# LIC_rack_TS-01.net
KiCad netlist of a schematic drawn in EAGLE
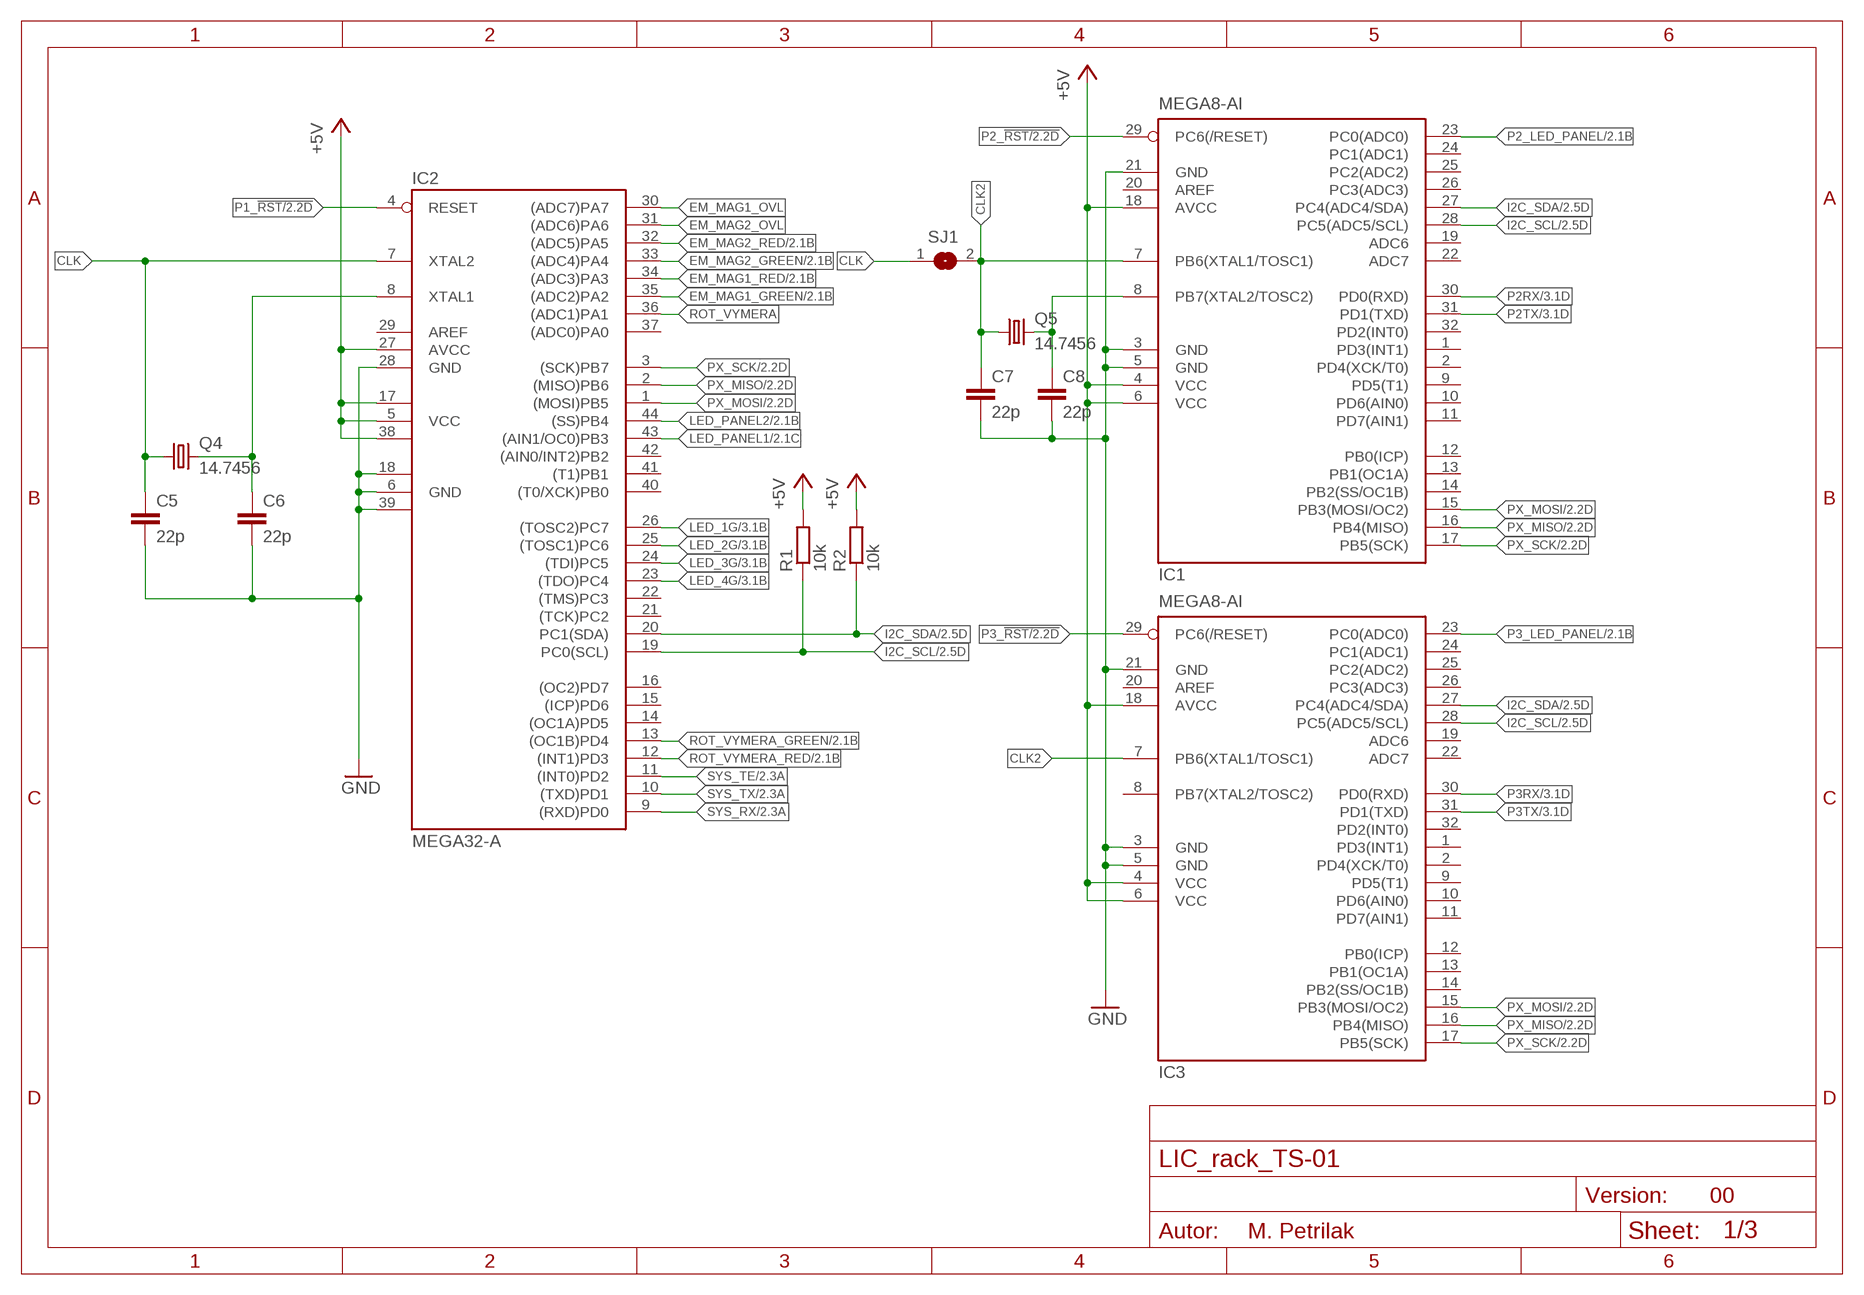
[diagram p0: schematic, sheet 1]
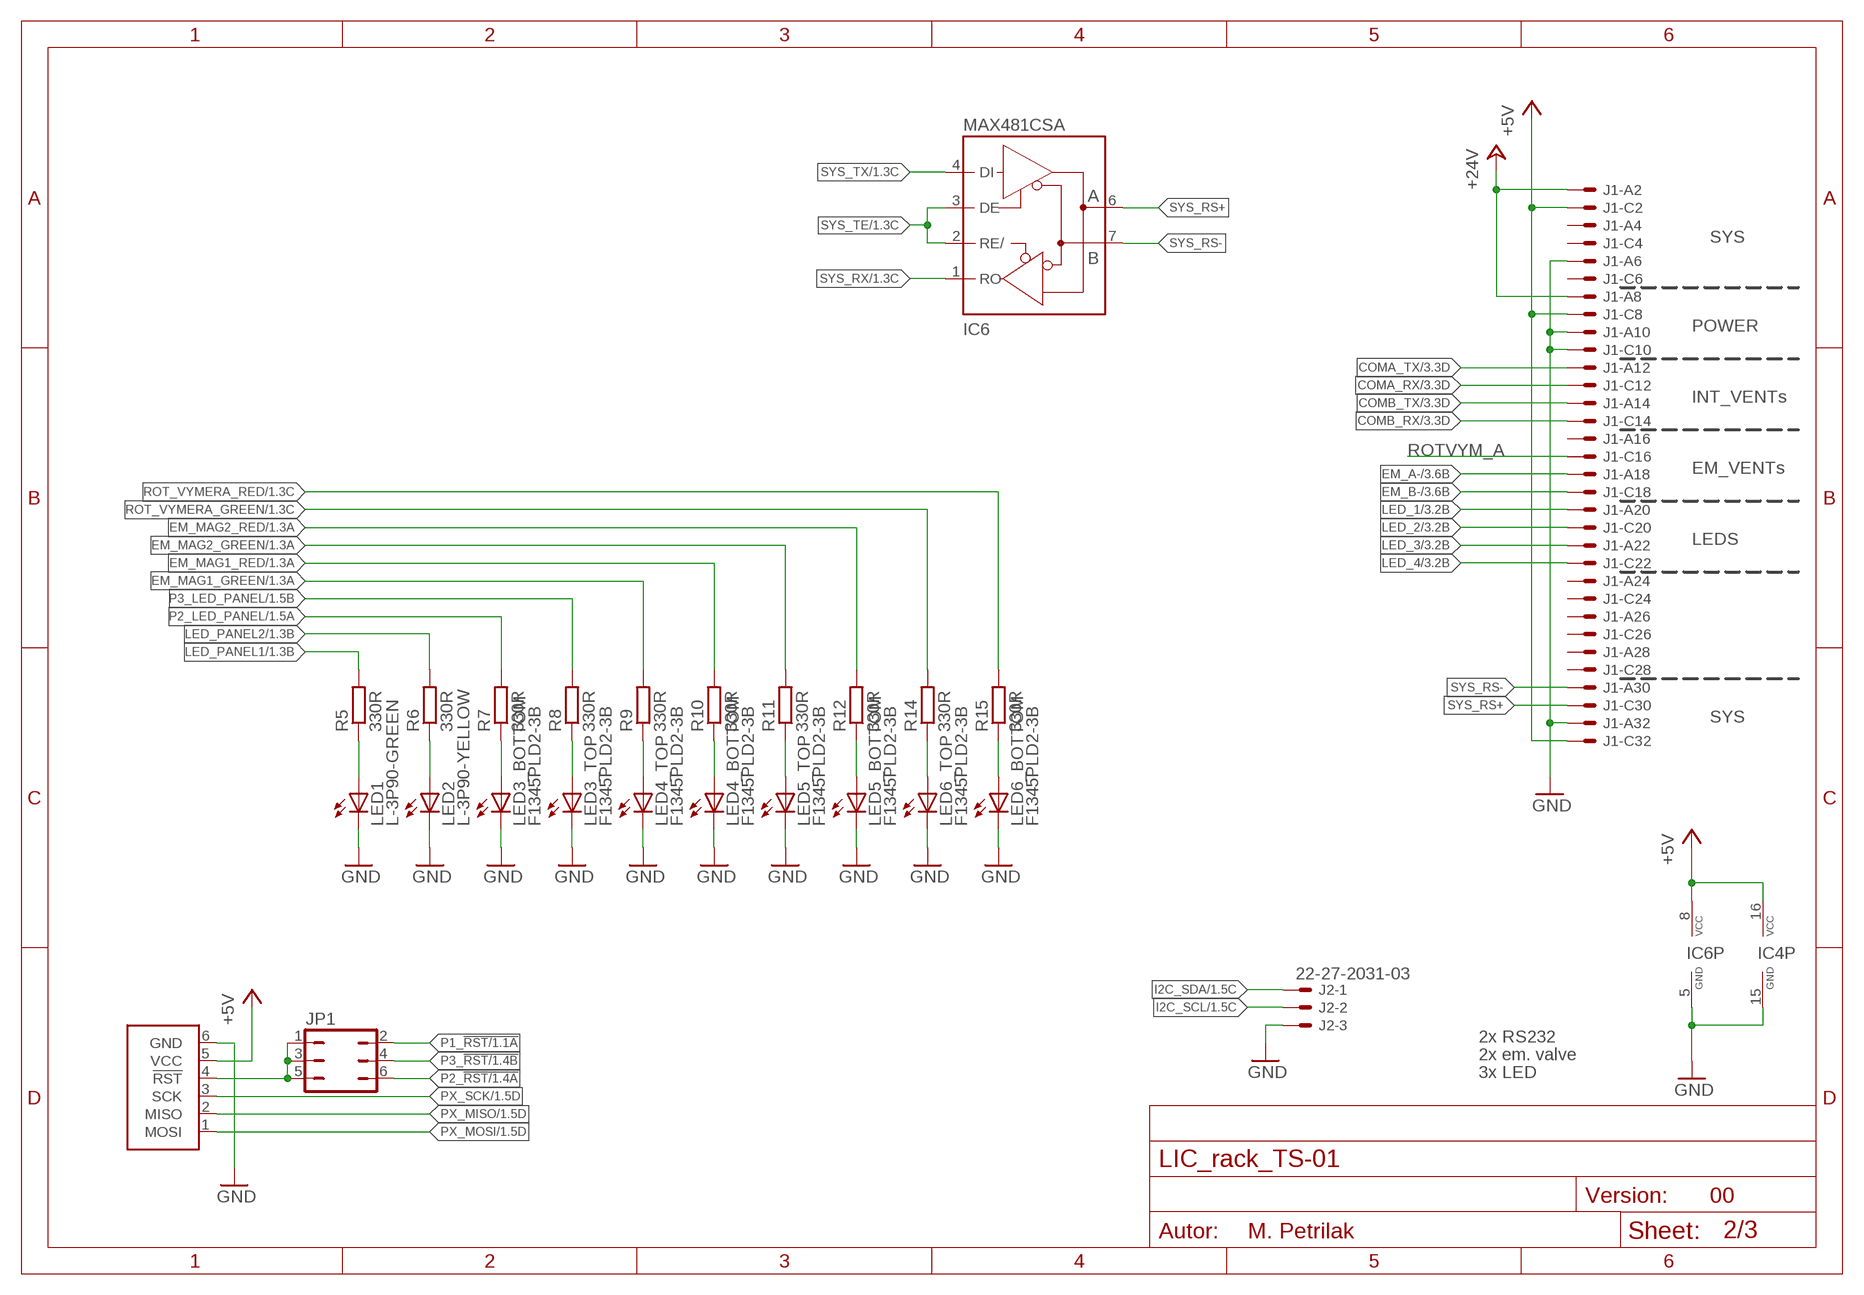
[diagram p1: schematic, sheet 2]
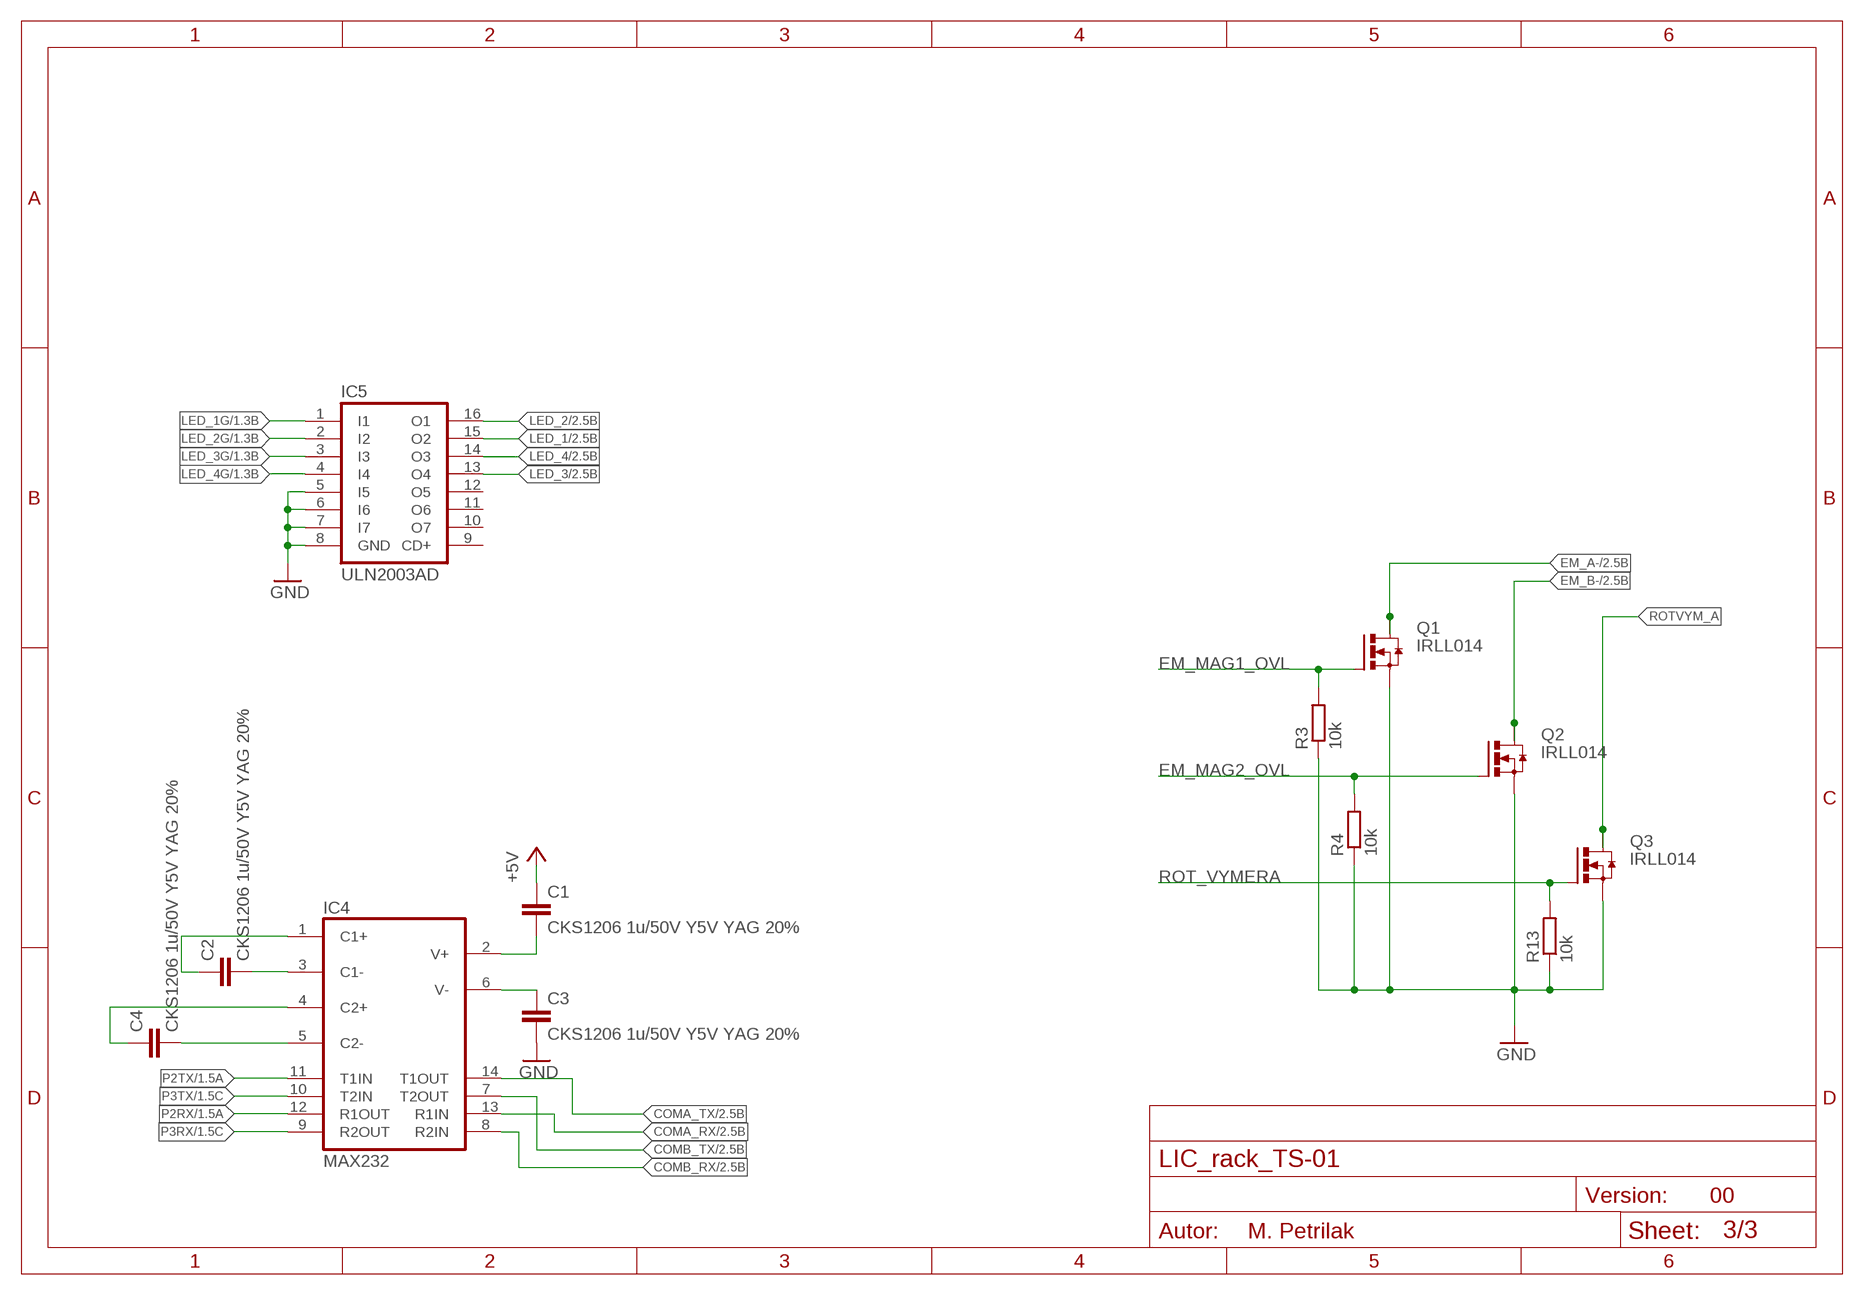
[diagram p2: schematic, sheet 3]

(export (version "E")
  (design (tool "Eeschema 10.0.6"))
  (components
    (comp (ref "C1")
      (value "CKS1206 1u/50V Y5V YAG 20%")
      (footprint "eagle-import:C1206")
      (libsource (lib "eagle-import") (part "C-EUC1206"))
    )
    (comp (ref "C2")
      (value "CKS1206 1u/50V Y5V YAG 20%")
      (footprint "eagle-import:C1206")
      (libsource (lib "eagle-import") (part "C-EUC1206"))
    )
    (comp (ref "C3")
      (value "CKS1206 1u/50V Y5V YAG 20%")
      (footprint "eagle-import:C1206")
      (libsource (lib "eagle-import") (part "C-EUC1206"))
    )
    (comp (ref "C4")
      (value "CKS1206 1u/50V Y5V YAG 20%")
      (footprint "eagle-import:C1206")
      (libsource (lib "eagle-import") (part "C-EUC1206"))
    )
    (comp (ref "IC4")
      (value "MAX232")
      (footprint "eagle-import:DIL16")
      (libsource (lib "eagle-import") (part "MAX232"))
    )
    (comp (ref "IC5")
      (value "ULN2003AD")
      (footprint "eagle-import:SO16")
      (libsource (lib "eagle-import") (part "ULN2003AD"))
    )
    (comp (ref "Q1")
      (value "IRLL014")
      (footprint "eagle-import:SOT223")
      (libsource (lib "eagle-import") (part "IRLL014"))
    )
    (comp (ref "Q2")
      (value "IRLL014")
      (footprint "eagle-import:SOT223")
      (libsource (lib "eagle-import") (part "IRLL014"))
    )
    (comp (ref "Q3")
      (value "IRLL014")
      (footprint "eagle-import:SOT223")
      (libsource (lib "eagle-import") (part "IRLL014"))
    )
    (comp (ref "R3")
      (value "10k")
      (footprint "eagle-import:R1206")
      (libsource (lib "eagle-import") (part "R-EU_R1206"))
    )
    (comp (ref "R4")
      (value "10k")
      (footprint "eagle-import:R1206")
      (libsource (lib "eagle-import") (part "R-EU_R1206"))
    )
    (comp (ref "R13")
      (value "10k")
      (footprint "eagle-import:R1206")
      (libsource (lib "eagle-import") (part "R-EU_R1206"))
    )
    (comp (ref "C5")
      (value "22p")
      (footprint "eagle-import:C0805")
      (libsource (lib "eagle-import") (part "C-EUC0805"))
    )
    (comp (ref "C6")
      (value "22p")
      (footprint "eagle-import:C0805")
      (libsource (lib "eagle-import") (part "C-EUC0805"))
    )
    (comp (ref "C7")
      (value "22p")
      (footprint "eagle-import:C0805")
      (libsource (lib "eagle-import") (part "C-EUC0805"))
    )
    (comp (ref "C8")
      (value "22p")
      (footprint "eagle-import:C0805")
      (libsource (lib "eagle-import") (part "C-EUC0805"))
    )
    (comp (ref "IC1")
      (value "MEGA8-AI")
      (footprint "eagle-import:TQFP32-08")
      (libsource (lib "eagle-import") (part "MEGA8-AI"))
    )
    (comp (ref "IC2")
      (value "MEGA32-A")
      (footprint "eagle-import:TQFP44")
      (libsource (lib "eagle-import") (part "MEGA32-A"))
    )
    (comp (ref "IC3")
      (value "MEGA8-AI")
      (footprint "eagle-import:TQFP32-08")
      (libsource (lib "eagle-import") (part "MEGA8-AI"))
    )
    (comp (ref "Q4")
      (value "14.7456")
      (footprint "eagle-import:HC49U70")
      (libsource (lib "eagle-import") (part "XTAL"))
    )
    (comp (ref "Q5")
      (value "14.7456")
      (footprint "eagle-import:HC49U70")
      (libsource (lib "eagle-import") (part "XTAL"))
    )
    (comp (ref "R1")
      (value "10k")
      (footprint "eagle-import:R1206")
      (libsource (lib "eagle-import") (part "R-EU_R1206"))
    )
    (comp (ref "R2")
      (value "10k")
      (footprint "eagle-import:R1206")
      (libsource (lib "eagle-import") (part "R-EU_R1206"))
    )
    (comp (ref "SJ1")
      (value "SJ-DEFAULT")
      (footprint "eagle-import:SJ-D")
      (libsource (lib "eagle-import") (part "SJ-DEFAULT"))
    )
    (comp (ref "IC6")
      (value "MAX481CSA")
      (footprint "eagle-import:SO08")
      (libsource (lib "eagle-import") (part "MAX481CSA"))
    )
    (comp (ref "J1")
      (value "VG32SP")
      (footprint "eagle-import:VG32P")
      (libsource (lib "eagle-import") (part "VG32SP"))
    )
    (comp (ref "J2")
      (value "22-27-2031-03")
      (footprint "eagle-import:6410-03")
      (libsource (lib "eagle-import") (part "22-?-0327-2031"))
    )
    (comp (ref "JP1")
      (value "JP3Q")
      (footprint "eagle-import:JP3Q")
      (libsource (lib "eagle-import") (part "JP3Q"))
    )
    (comp (ref "LED1")
      (value "L-3P90-GREEN")
      (footprint "eagle-import:L-3P90")
      (libsource (lib "eagle-import") (part "L-3P90-GREEN"))
    )
    (comp (ref "LED2")
      (value "L-3P90-YELLOW")
      (footprint "eagle-import:L-3P90")
      (libsource (lib "eagle-import") (part "L-3P90-YELLOW"))
    )
    (comp (ref "LED3")
      (value "F1345PLD2-3B")
      (footprint "eagle-import:F1345PLD2-3B")
      (libsource (lib "eagle-import") (part "F1345PLD2-3B"))
    )
    (comp (ref "LED4")
      (value "F1345PLD2-3B")
      (footprint "eagle-import:F1345PLD2-3B")
      (libsource (lib "eagle-import") (part "F1345PLD2-3B"))
    )
    (comp (ref "LED5")
      (value "F1345PLD2-3B")
      (footprint "eagle-import:F1345PLD2-3B")
      (libsource (lib "eagle-import") (part "F1345PLD2-3B"))
    )
    (comp (ref "LED6")
      (value "F1345PLD2-3B")
      (footprint "eagle-import:F1345PLD2-3B")
      (libsource (lib "eagle-import") (part "F1345PLD2-3B"))
    )
    (comp (ref "R5")
      (value "330R")
      (footprint "eagle-import:R1206")
      (libsource (lib "eagle-import") (part "R-EU_R1206"))
    )
    (comp (ref "R6")
      (value "330R")
      (footprint "eagle-import:R1206")
      (libsource (lib "eagle-import") (part "R-EU_R1206"))
    )
    (comp (ref "R7")
      (value "330R")
      (footprint "eagle-import:R1206")
      (libsource (lib "eagle-import") (part "R-EU_R1206"))
    )
    (comp (ref "R8")
      (value "330R")
      (footprint "eagle-import:R1206")
      (libsource (lib "eagle-import") (part "R-EU_R1206"))
    )
    (comp (ref "R9")
      (value "330R")
      (footprint "eagle-import:R1206")
      (libsource (lib "eagle-import") (part "R-EU_R1206"))
    )
    (comp (ref "R10")
      (value "330R")
      (footprint "eagle-import:R1206")
      (libsource (lib "eagle-import") (part "R-EU_R1206"))
    )
    (comp (ref "R11")
      (value "330R")
      (footprint "eagle-import:R1206")
      (libsource (lib "eagle-import") (part "R-EU_R1206"))
    )
    (comp (ref "R12")
      (value "330R")
      (footprint "eagle-import:R1206")
      (libsource (lib "eagle-import") (part "R-EU_R1206"))
    )
    (comp (ref "R14")
      (value "330R")
      (footprint "eagle-import:R1206")
      (libsource (lib "eagle-import") (part "R-EU_R1206"))
    )
    (comp (ref "R15")
      (value "330R")
      (footprint "eagle-import:R1206")
      (libsource (lib "eagle-import") (part "R-EU_R1206"))
    )
    (comp (ref "U1")
      (value "ATPROG-V")
      (footprint "eagle-import:6410-06")
      (libsource (lib "eagle-import") (part "ATPROG-V"))
    )
  )
  (nets
    (net (code "1") (name "+5V") (class "Default")
      (node (ref "C1") (pin "1") (pinfunction "1_1") (pintype "passive"))
      (node (ref "IC1") (pin "18") (pinfunction "AVCC_18") (pintype "power_in"))
      (node (ref "IC1") (pin "4") (pinfunction "VCC_4") (pintype "power_in"))
      (node (ref "IC1") (pin "6") (pinfunction "VCC_6") (pintype "power_in"))
      (node (ref "IC2") (pin "17") (pinfunction "VCC1_17") (pintype "power_in"))
      (node (ref "IC2") (pin "27") (pinfunction "AVCC_27") (pintype "power_in"))
      (node (ref "IC2") (pin "38") (pinfunction "VCC2_38") (pintype "power_in"))
      (node (ref "IC2") (pin "5") (pinfunction "VCC_5") (pintype "power_in"))
      (node (ref "IC3") (pin "18") (pinfunction "AVCC_18") (pintype "power_in"))
      (node (ref "IC3") (pin "4") (pinfunction "VCC_4") (pintype "power_in"))
      (node (ref "IC3") (pin "6") (pinfunction "VCC_6") (pintype "power_in"))
      (node (ref "IC4") (pin "16") (pinfunction "VCC_16") (pintype "power_in"))
      (node (ref "IC6") (pin "8") (pinfunction "VCC_8") (pintype "power_in"))
      (node (ref "J1") (pin "C2") (pinfunction "MS_C2") (pintype "passive"))
      (node (ref "J1") (pin "C32") (pinfunction "MSV_C32") (pintype "passive"))
      (node (ref "J1") (pin "C8") (pinfunction "MS_C8") (pintype "passive"))
      (node (ref "R1") (pin "2") (pinfunction "2_2") (pintype "passive"))
      (node (ref "R2") (pin "2") (pinfunction "2_2") (pintype "passive"))
      (node (ref "U1") (pin "5") (pinfunction "VCC_5") (pintype "power_in"))
    )
    (net (code "2") (name "+24V") (class "Default")
      (node (ref "J1") (pin "A2") (pinfunction "MS_A2") (pintype "passive"))
      (node (ref "J1") (pin "A8") (pinfunction "MS_A8") (pintype "passive"))
    )
    (net (code "3") (name "CLK") (class "Default")
      (node (ref "C5") (pin "1") (pinfunction "1_1") (pintype "passive"))
      (node (ref "IC2") (pin "7") (pinfunction "XTAL2_7") (pintype "bidirectional"))
      (node (ref "Q4") (pin "1") (pinfunction "1_1") (pintype "passive"))
      (node (ref "SJ1") (pin "1") (pinfunction "1_1") (pintype "passive"))
    )
    (net (code "4") (name "CLK2") (class "Default")
      (node (ref "C7") (pin "1") (pinfunction "1_1") (pintype "passive"))
      (node (ref "IC1") (pin "7") (pinfunction "PB6(XTAL1/TOSC1)_7") (pintype "bidirectional"))
      (node (ref "IC3") (pin "7") (pinfunction "PB6(XTAL1/TOSC1)_7") (pintype "bidirectional"))
      (node (ref "Q5") (pin "1") (pinfunction "1_1") (pintype "passive"))
      (node (ref "SJ1") (pin "2") (pinfunction "2_2") (pintype "passive"))
    )
    (net (code "5") (name "COMA_RX") (class "Default")
      (node (ref "IC4") (pin "13") (pinfunction "R1IN_13") (pintype "input"))
      (node (ref "J1") (pin "C12") (pinfunction "MS_C12") (pintype "passive"))
    )
    (net (code "6") (name "COMA_TX") (class "Default")
      (node (ref "IC4") (pin "14") (pinfunction "T1OUT_14") (pintype "output"))
      (node (ref "J1") (pin "A12") (pinfunction "MS_A12") (pintype "passive"))
    )
    (net (code "7") (name "COMB_RX") (class "Default")
      (node (ref "IC4") (pin "8") (pinfunction "R2IN_8") (pintype "input"))
      (node (ref "J1") (pin "C14") (pinfunction "MS_C14") (pintype "passive"))
    )
    (net (code "8") (name "COMB_TX") (class "Default")
      (node (ref "IC4") (pin "7") (pinfunction "T2OUT_7") (pintype "output"))
      (node (ref "J1") (pin "A14") (pinfunction "MS_A14") (pintype "passive"))
    )
    (net (code "9") (name "EM_A-") (class "Default")
      (node (ref "J1") (pin "A18") (pinfunction "MS_A18") (pintype "passive"))
      (node (ref "Q1") (pin "2") (pinfunction "D_2") (pintype "passive"))
      (node (ref "Q1") (pin "4") (pinfunction "D_4") (pintype "passive"))
    )
    (net (code "10") (name "EM_B-") (class "Default")
      (node (ref "J1") (pin "C18") (pinfunction "MS_C18") (pintype "passive"))
      (node (ref "Q2") (pin "2") (pinfunction "D_2") (pintype "passive"))
      (node (ref "Q2") (pin "4") (pinfunction "D_4") (pintype "passive"))
    )
    (net (code "11") (name "EM_MAG1_GREEN") (class "Default")
      (node (ref "IC2") (pin "35") (pinfunction "(ADC2)PA2_35") (pintype "bidirectional"))
      (node (ref "R9") (pin "2") (pinfunction "2_2") (pintype "passive"))
    )
    (net (code "12") (name "EM_MAG1_OVL") (class "Default")
      (node (ref "IC2") (pin "30") (pinfunction "(ADC7)PA7_30") (pintype "bidirectional"))
      (node (ref "Q1") (pin "1") (pinfunction "G_1") (pintype "passive"))
      (node (ref "R3") (pin "2") (pinfunction "2_2") (pintype "passive"))
    )
    (net (code "13") (name "EM_MAG1_RED") (class "Default")
      (node (ref "IC2") (pin "34") (pinfunction "(ADC3)PA3_34") (pintype "bidirectional"))
      (node (ref "R10") (pin "2") (pinfunction "2_2") (pintype "passive"))
    )
    (net (code "14") (name "EM_MAG2_GREEN") (class "Default")
      (node (ref "IC2") (pin "33") (pinfunction "(ADC4)PA4_33") (pintype "bidirectional"))
      (node (ref "R11") (pin "2") (pinfunction "2_2") (pintype "passive"))
    )
    (net (code "15") (name "EM_MAG2_OVL") (class "Default")
      (node (ref "IC2") (pin "31") (pinfunction "(ADC6)PA6_31") (pintype "bidirectional"))
      (node (ref "Q2") (pin "1") (pinfunction "G_1") (pintype "passive"))
      (node (ref "R4") (pin "2") (pinfunction "2_2") (pintype "passive"))
    )
    (net (code "16") (name "EM_MAG2_RED") (class "Default")
      (node (ref "IC2") (pin "32") (pinfunction "(ADC5)PA5_32") (pintype "bidirectional"))
      (node (ref "R12") (pin "2") (pinfunction "2_2") (pintype "passive"))
    )
    (net (code "17") (name "GND") (class "Default")
      (node (ref "C3") (pin "2") (pinfunction "2_2") (pintype "passive"))
      (node (ref "C5") (pin "2") (pinfunction "2_2") (pintype "passive"))
      (node (ref "C6") (pin "2") (pinfunction "2_2") (pintype "passive"))
      (node (ref "C7") (pin "2") (pinfunction "2_2") (pintype "passive"))
      (node (ref "C8") (pin "2") (pinfunction "2_2") (pintype "passive"))
      (node (ref "IC1") (pin "21") (pinfunction "GND_21") (pintype "power_in"))
      (node (ref "IC1") (pin "3") (pinfunction "GND_3") (pintype "power_in"))
      (node (ref "IC1") (pin "5") (pinfunction "GND_5") (pintype "power_in"))
      (node (ref "IC2") (pin "18") (pinfunction "GND1_18") (pintype "power_in"))
      (node (ref "IC2") (pin "28") (pinfunction "GND_28") (pintype "power_in"))
      (node (ref "IC2") (pin "39") (pinfunction "GND2_39") (pintype "power_in"))
      (node (ref "IC2") (pin "6") (pinfunction "GND_6") (pintype "power_in"))
      (node (ref "IC3") (pin "21") (pinfunction "GND_21") (pintype "power_in"))
      (node (ref "IC3") (pin "3") (pinfunction "GND_3") (pintype "power_in"))
      (node (ref "IC3") (pin "5") (pinfunction "GND_5") (pintype "power_in"))
      (node (ref "IC4") (pin "15") (pinfunction "GND_15") (pintype "power_in"))
      (node (ref "IC5") (pin "5") (pinfunction "I5_5") (pintype "input"))
      (node (ref "IC5") (pin "6") (pinfunction "I6_6") (pintype "input"))
      (node (ref "IC5") (pin "7") (pinfunction "I7_7") (pintype "input"))
      (node (ref "IC5") (pin "8") (pinfunction "GND_8") (pintype "power_in"))
      (node (ref "IC6") (pin "5") (pinfunction "GND_5") (pintype "power_in"))
      (node (ref "J1") (pin "A10") (pinfunction "MS_A10") (pintype "passive"))
      (node (ref "J1") (pin "A32") (pinfunction "MS_A32") (pintype "passive"))
      (node (ref "J1") (pin "A6") (pinfunction "MS_A6") (pintype "passive"))
      (node (ref "J1") (pin "C10") (pinfunction "MS_C10") (pintype "passive"))
      (node (ref "J2") (pin "3") (pinfunction "S_3") (pintype "passive"))
      (node (ref "LED1") (pin "K") (pinfunction "C_K") (pintype "passive"))
      (node (ref "LED2") (pin "K") (pinfunction "C_K") (pintype "passive"))
      (node (ref "LED3") (pin "1K") (pinfunction "C_1K") (pintype "passive"))
      (node (ref "LED3") (pin "2K") (pinfunction "C_2K") (pintype "passive"))
      (node (ref "LED4") (pin "1K") (pinfunction "C_1K") (pintype "passive"))
      (node (ref "LED4") (pin "2K") (pinfunction "C_2K") (pintype "passive"))
      (node (ref "LED5") (pin "1K") (pinfunction "C_1K") (pintype "passive"))
      (node (ref "LED5") (pin "2K") (pinfunction "C_2K") (pintype "passive"))
      (node (ref "LED6") (pin "1K") (pinfunction "C_1K") (pintype "passive"))
      (node (ref "LED6") (pin "2K") (pinfunction "C_2K") (pintype "passive"))
      (node (ref "Q1") (pin "3") (pinfunction "S_3") (pintype "passive"))
      (node (ref "Q2") (pin "3") (pinfunction "S_3") (pintype "passive"))
      (node (ref "Q3") (pin "3") (pinfunction "S_3") (pintype "passive"))
      (node (ref "R13") (pin "1") (pinfunction "1_1") (pintype "passive"))
      (node (ref "R3") (pin "1") (pinfunction "1_1") (pintype "passive"))
      (node (ref "R4") (pin "1") (pinfunction "1_1") (pintype "passive"))
      (node (ref "U1") (pin "6") (pinfunction "GND_6") (pintype "power_in"))
    )
    (net (code "18") (name "I2C_SCL") (class "Default")
      (node (ref "IC1") (pin "28") (pinfunction "PC5(ADC5/SCL)_28") (pintype "bidirectional"))
      (node (ref "IC2") (pin "19") (pinfunction "PC0(SCL)_19") (pintype "bidirectional"))
      (node (ref "IC3") (pin "28") (pinfunction "PC5(ADC5/SCL)_28") (pintype "bidirectional"))
      (node (ref "J2") (pin "2") (pinfunction "S_2") (pintype "passive"))
      (node (ref "R1") (pin "1") (pinfunction "1_1") (pintype "passive"))
    )
    (net (code "19") (name "I2C_SDA") (class "Default")
      (node (ref "IC1") (pin "27") (pinfunction "PC4(ADC4/SDA)_27") (pintype "bidirectional"))
      (node (ref "IC2") (pin "20") (pinfunction "PC1(SDA)_20") (pintype "bidirectional"))
      (node (ref "IC3") (pin "27") (pinfunction "PC4(ADC4/SDA)_27") (pintype "bidirectional"))
      (node (ref "J2") (pin "1") (pinfunction "S_1") (pintype "passive"))
      (node (ref "R2") (pin "1") (pinfunction "1_1") (pintype "passive"))
    )
    (net (code "20") (name "LED_1") (class "Default")
      (node (ref "IC5") (pin "15") (pinfunction "O2_15") (pintype "open_collector"))
      (node (ref "J1") (pin "A20") (pinfunction "MS_A20") (pintype "passive"))
    )
    (net (code "21") (name "LED_1G") (class "Default")
      (node (ref "IC2") (pin "26") (pinfunction "(TOSC2)PC7_26") (pintype "bidirectional"))
      (node (ref "IC5") (pin "1") (pinfunction "I1_1") (pintype "input"))
    )
    (net (code "22") (name "LED_2") (class "Default")
      (node (ref "IC5") (pin "16") (pinfunction "O1_16") (pintype "open_collector"))
      (node (ref "J1") (pin "C20") (pinfunction "MS_C20") (pintype "passive"))
    )
    (net (code "23") (name "LED_2G") (class "Default")
      (node (ref "IC2") (pin "25") (pinfunction "(TOSC1)PC6_25") (pintype "bidirectional"))
      (node (ref "IC5") (pin "2") (pinfunction "I2_2") (pintype "input"))
    )
    (net (code "24") (name "LED_3") (class "Default")
      (node (ref "IC5") (pin "13") (pinfunction "O4_13") (pintype "open_collector"))
      (node (ref "J1") (pin "A22") (pinfunction "MS_A22") (pintype "passive"))
    )
    (net (code "25") (name "LED_3G") (class "Default")
      (node (ref "IC2") (pin "24") (pinfunction "(TDI)PC5_24") (pintype "bidirectional"))
      (node (ref "IC5") (pin "3") (pinfunction "I3_3") (pintype "input"))
    )
    (net (code "26") (name "LED_4") (class "Default")
      (node (ref "IC5") (pin "14") (pinfunction "O3_14") (pintype "open_collector"))
      (node (ref "J1") (pin "C22") (pinfunction "MS_C22") (pintype "passive"))
    )
    (net (code "27") (name "LED_4G") (class "Default")
      (node (ref "IC2") (pin "23") (pinfunction "(TDO)PC4_23") (pintype "bidirectional"))
      (node (ref "IC5") (pin "4") (pinfunction "I4_4") (pintype "input"))
    )
    (net (code "28") (name "LED_PANEL1") (class "Default")
      (node (ref "IC2") (pin "43") (pinfunction "(AIN1/OC0)PB3_43") (pintype "bidirectional"))
      (node (ref "R5") (pin "2") (pinfunction "2_2") (pintype "passive"))
    )
    (net (code "29") (name "LED_PANEL2") (class "Default")
      (node (ref "IC2") (pin "44") (pinfunction "(SS)PB4_44") (pintype "bidirectional"))
      (node (ref "R6") (pin "2") (pinfunction "2_2") (pintype "passive"))
    )
    (net (code "30") (name "Net-(IC1-PB7(XTAL2{slash}TOSC2))") (class "Default")
      (node (ref "C8") (pin "1") (pinfunction "1_1") (pintype "passive"))
      (node (ref "IC1") (pin "8") (pinfunction "PB7(XTAL2/TOSC2)_8") (pintype "bidirectional"))
      (node (ref "Q5") (pin "2") (pinfunction "2_2") (pintype "passive"))
    )
    (net (code "31") (name "Net-(IC2-XTAL1)") (class "Default")
      (node (ref "C6") (pin "1") (pinfunction "1_1") (pintype "passive"))
      (node (ref "IC2") (pin "8") (pinfunction "XTAL1_8") (pintype "bidirectional"))
      (node (ref "Q4") (pin "2") (pinfunction "2_2") (pintype "passive"))
    )
    (net (code "32") (name "Net-(IC4A-C1+)") (class "Default")
      (node (ref "C2") (pin "1") (pinfunction "1_1") (pintype "passive"))
      (node (ref "IC4") (pin "1") (pinfunction "C1+_1") (pintype "bidirectional"))
    )
    (net (code "33") (name "Net-(IC4A-C1-)") (class "Default")
      (node (ref "C2") (pin "2") (pinfunction "2_2") (pintype "passive"))
      (node (ref "IC4") (pin "3") (pinfunction "C1-_3") (pintype "bidirectional"))
    )
    (net (code "34") (name "Net-(IC4A-C2+)") (class "Default")
      (node (ref "C4") (pin "1") (pinfunction "1_1") (pintype "passive"))
      (node (ref "IC4") (pin "4") (pinfunction "C2+_4") (pintype "bidirectional"))
    )
    (net (code "35") (name "Net-(IC4A-C2-)") (class "Default")
      (node (ref "C4") (pin "2") (pinfunction "2_2") (pintype "passive"))
      (node (ref "IC4") (pin "5") (pinfunction "C2-_5") (pintype "bidirectional"))
    )
    (net (code "36") (name "Net-(IC4A-V+)") (class "Default")
      (node (ref "C1") (pin "2") (pinfunction "2_2") (pintype "passive"))
      (node (ref "IC4") (pin "2") (pinfunction "V+_2") (pintype "bidirectional"))
    )
    (net (code "37") (name "Net-(IC4A-V-)") (class "Default")
      (node (ref "C3") (pin "1") (pinfunction "1_1") (pintype "passive"))
      (node (ref "IC4") (pin "6") (pinfunction "V-_6") (pintype "bidirectional"))
    )
    (net (code "38") (name "Net-(LED1-PadA)") (class "Default")
      (node (ref "LED1") (pin "A") (pinfunction "A_A") (pintype "passive"))
      (node (ref "R5") (pin "1") (pinfunction "1_1") (pintype "passive"))
    )
    (net (code "39") (name "Net-(LED2-PadA)") (class "Default")
      (node (ref "LED2") (pin "A") (pinfunction "A_A") (pintype "passive"))
      (node (ref "R6") (pin "1") (pinfunction "1_1") (pintype "passive"))
    )
    (net (code "40") (name "Net-(LED3A-A)") (class "Default")
      (node (ref "LED3") (pin "1A") (pinfunction "A_1A") (pintype "passive"))
      (node (ref "R7") (pin "1") (pinfunction "1_1") (pintype "passive"))
    )
    (net (code "41") (name "Net-(LED3B-A)") (class "Default")
      (node (ref "LED3") (pin "2A") (pinfunction "A_2A") (pintype "passive"))
      (node (ref "R8") (pin "1") (pinfunction "1_1") (pintype "passive"))
    )
    (net (code "42") (name "Net-(LED4A-A)") (class "Default")
      (node (ref "LED4") (pin "1A") (pinfunction "A_1A") (pintype "passive"))
      (node (ref "R10") (pin "1") (pinfunction "1_1") (pintype "passive"))
    )
    (net (code "43") (name "Net-(LED4B-A)") (class "Default")
      (node (ref "LED4") (pin "2A") (pinfunction "A_2A") (pintype "passive"))
      (node (ref "R9") (pin "1") (pinfunction "1_1") (pintype "passive"))
    )
    (net (code "44") (name "Net-(LED5A-A)") (class "Default")
      (node (ref "LED5") (pin "1A") (pinfunction "A_1A") (pintype "passive"))
      (node (ref "R12") (pin "1") (pinfunction "1_1") (pintype "passive"))
    )
    (net (code "45") (name "Net-(LED5B-A)") (class "Default")
      (node (ref "LED5") (pin "2A") (pinfunction "A_2A") (pintype "passive"))
      (node (ref "R11") (pin "1") (pinfunction "1_1") (pintype "passive"))
    )
    (net (code "46") (name "Net-(LED6A-A)") (class "Default")
      (node (ref "LED6") (pin "1A") (pinfunction "A_1A") (pintype "passive"))
      (node (ref "R15") (pin "1") (pinfunction "1_1") (pintype "passive"))
    )
    (net (code "47") (name "Net-(LED6B-A)") (class "Default")
      (node (ref "LED6") (pin "2A") (pinfunction "A_2A") (pintype "passive"))
      (node (ref "R14") (pin "1") (pinfunction "1_1") (pintype "passive"))
    )
    (net (code "48") (name "Net-(U1-~{RST})") (class "Default")
      (node (ref "JP1") (pin "1") (pinfunction "1_1") (pintype "passive"))
      (node (ref "JP1") (pin "3") (pinfunction "3_3") (pintype "passive"))
      (node (ref "JP1") (pin "5") (pinfunction "5_5") (pintype "passive"))
      (node (ref "U1") (pin "4") (pinfunction "~{RST}_4") (pintype "input"))
    )
    (net (code "49") (name "P1_~{RST}") (class "Default")
      (node (ref "IC2") (pin "4") (pinfunction "RESET_4") (pintype "input"))
      (node (ref "JP1") (pin "2") (pinfunction "2_2") (pintype "passive"))
    )
    (net (code "50") (name "P2RX") (class "Default")
      (node (ref "IC1") (pin "30") (pinfunction "PD0(RXD)_30") (pintype "bidirectional"))
      (node (ref "IC4") (pin "12") (pinfunction "R1OUT_12") (pintype "output"))
    )
    (net (code "51") (name "P2TX") (class "Default")
      (node (ref "IC1") (pin "31") (pinfunction "PD1(TXD)_31") (pintype "bidirectional"))
      (node (ref "IC4") (pin "11") (pinfunction "T1IN_11") (pintype "input"))
    )
    (net (code "52") (name "P2_LED_PANEL") (class "Default")
      (node (ref "IC1") (pin "23") (pinfunction "PC0(ADC0)_23") (pintype "bidirectional"))
      (node (ref "R7") (pin "2") (pinfunction "2_2") (pintype "passive"))
    )
    (net (code "53") (name "P2_~{RST}") (class "Default")
      (node (ref "IC1") (pin "29") (pinfunction "PC6(/RESET)_29") (pintype "bidirectional"))
      (node (ref "JP1") (pin "6") (pinfunction "6_6") (pintype "passive"))
    )
    (net (code "54") (name "P3RX") (class "Default")
      (node (ref "IC3") (pin "30") (pinfunction "PD0(RXD)_30") (pintype "bidirectional"))
      (node (ref "IC4") (pin "9") (pinfunction "R2OUT_9") (pintype "output"))
    )
    (net (code "55") (name "P3TX") (class "Default")
      (node (ref "IC3") (pin "31") (pinfunction "PD1(TXD)_31") (pintype "bidirectional"))
      (node (ref "IC4") (pin "10") (pinfunction "T2IN_10") (pintype "input"))
    )
    (net (code "56") (name "P3_LED_PANEL") (class "Default")
      (node (ref "IC3") (pin "23") (pinfunction "PC0(ADC0)_23") (pintype "bidirectional"))
      (node (ref "R8") (pin "2") (pinfunction "2_2") (pintype "passive"))
    )
    (net (code "57") (name "P3_~{RST}") (class "Default")
      (node (ref "IC3") (pin "29") (pinfunction "PC6(/RESET)_29") (pintype "bidirectional"))
      (node (ref "JP1") (pin "4") (pinfunction "4_4") (pintype "passive"))
    )
    (net (code "58") (name "PX_MISO") (class "Default")
      (node (ref "IC1") (pin "16") (pinfunction "PB4(MISO)_16") (pintype "bidirectional"))
      (node (ref "IC2") (pin "2") (pinfunction "(MISO)PB6_2") (pintype "bidirectional"))
      (node (ref "IC3") (pin "16") (pinfunction "PB4(MISO)_16") (pintype "bidirectional"))
      (node (ref "U1") (pin "2") (pinfunction "MISO_2") (pintype "input"))
    )
    (net (code "59") (name "PX_MOSI") (class "Default")
      (node (ref "IC1") (pin "15") (pinfunction "PB3(MOSI/OC2)_15") (pintype "bidirectional"))
      (node (ref "IC2") (pin "1") (pinfunction "(MOSI)PB5_1") (pintype "bidirectional"))
      (node (ref "IC3") (pin "15") (pinfunction "PB3(MOSI/OC2)_15") (pintype "bidirectional"))
      (node (ref "U1") (pin "1") (pinfunction "MOSI_1") (pintype "output"))
    )
    (net (code "60") (name "PX_SCK") (class "Default")
      (node (ref "IC1") (pin "17") (pinfunction "PB5(SCK)_17") (pintype "bidirectional"))
      (node (ref "IC2") (pin "3") (pinfunction "(SCK)PB7_3") (pintype "bidirectional"))
      (node (ref "IC3") (pin "17") (pinfunction "PB5(SCK)_17") (pintype "bidirectional"))
      (node (ref "U1") (pin "3") (pinfunction "SCK_3") (pintype "input"))
    )
    (net (code "61") (name "ROTVYM_A") (class "Default")
      (node (ref "J1") (pin "C16") (pinfunction "MS_C16") (pintype "passive"))
      (node (ref "Q3") (pin "2") (pinfunction "D_2") (pintype "passive"))
      (node (ref "Q3") (pin "4") (pinfunction "D_4") (pintype "passive"))
    )
    (net (code "62") (name "ROT_VYMERA") (class "Default")
      (node (ref "IC2") (pin "36") (pinfunction "(ADC1)PA1_36") (pintype "bidirectional"))
      (node (ref "Q3") (pin "1") (pinfunction "G_1") (pintype "passive"))
      (node (ref "R13") (pin "2") (pinfunction "2_2") (pintype "passive"))
    )
    (net (code "63") (name "ROT_VYMERA_GREEN") (class "Default")
      (node (ref "IC2") (pin "13") (pinfunction "(OC1B)PD4_13") (pintype "bidirectional"))
      (node (ref "R14") (pin "2") (pinfunction "2_2") (pintype "passive"))
    )
    (net (code "64") (name "ROT_VYMERA_RED") (class "Default")
      (node (ref "IC2") (pin "12") (pinfunction "(INT1)PD3_12") (pintype "bidirectional"))
      (node (ref "R15") (pin "2") (pinfunction "2_2") (pintype "passive"))
    )
    (net (code "65") (name "SYS_RS+") (class "Default")
      (node (ref "IC6") (pin "6") (pinfunction "A_6") (pintype "passive"))
      (node (ref "J1") (pin "C30") (pinfunction "MS_C30") (pintype "passive"))
    )
    (net (code "66") (name "SYS_RS-") (class "Default")
      (node (ref "IC6") (pin "7") (pinfunction "B_7") (pintype "passive"))
      (node (ref "J1") (pin "A30") (pinfunction "MS_A30") (pintype "passive"))
    )
    (net (code "67") (name "SYS_RX") (class "Default")
      (node (ref "IC2") (pin "9") (pinfunction "(RXD)PD0_9") (pintype "bidirectional"))
      (node (ref "IC6") (pin "1") (pinfunction "RO_1") (pintype "output"))
    )
    (net (code "68") (name "SYS_TE") (class "Default")
      (node (ref "IC2") (pin "11") (pinfunction "(INT0)PD2_11") (pintype "bidirectional"))
      (node (ref "IC6") (pin "2") (pinfunction "RE/_2") (pintype "input"))
      (node (ref "IC6") (pin "3") (pinfunction "DE_3") (pintype "input"))
    )
    (net (code "69") (name "SYS_TX") (class "Default")
      (node (ref "IC2") (pin "10") (pinfunction "(TXD)PD1_10") (pintype "bidirectional"))
      (node (ref "IC6") (pin "4") (pinfunction "DI_4") (pintype "input"))
    )
    (net (code "70") (name "unconnected-(IC1-ADC6-Pad19)") (class "Default")
      (node (ref "IC1") (pin "19") (pinfunction "ADC6_19") (pintype "bidirectional"))
    )
    (net (code "71") (name "unconnected-(IC1-ADC7-Pad22)") (class "Default")
      (node (ref "IC1") (pin "22") (pinfunction "ADC7_22") (pintype "bidirectional"))
    )
    (net (code "72") (name "unconnected-(IC1-AREF-Pad20)") (class "Default")
      (node (ref "IC1") (pin "20") (pinfunction "AREF_20") (pintype "passive"))
    )
    (net (code "73") (name "unconnected-(IC1-PB0(ICP)-Pad12)") (class "Default")
      (node (ref "IC1") (pin "12") (pinfunction "PB0(ICP)_12") (pintype "bidirectional"))
    )
    (net (code "74") (name "unconnected-(IC1-PB1(OC1A)-Pad13)") (class "Default")
      (node (ref "IC1") (pin "13") (pinfunction "PB1(OC1A)_13") (pintype "bidirectional"))
    )
    (net (code "75") (name "unconnected-(IC1-PB2(SS{slash}OC1B)-Pad14)") (class "Default")
      (node (ref "IC1") (pin "14") (pinfunction "PB2(SS/OC1B)_14") (pintype "bidirectional"))
    )
    (net (code "76") (name "unconnected-(IC1-PC1(ADC1)-Pad24)") (class "Default")
      (node (ref "IC1") (pin "24") (pinfunction "PC1(ADC1)_24") (pintype "bidirectional"))
    )
    (net (code "77") (name "unconnected-(IC1-PC2(ADC2)-Pad25)") (class "Default")
      (node (ref "IC1") (pin "25") (pinfunction "PC2(ADC2)_25") (pintype "bidirectional"))
    )
    (net (code "78") (name "unconnected-(IC1-PC3(ADC3)-Pad26)") (class "Default")
      (node (ref "IC1") (pin "26") (pinfunction "PC3(ADC3)_26") (pintype "bidirectional"))
    )
    (net (code "79") (name "unconnected-(IC1-PD2(INT0)-Pad32)") (class "Default")
      (node (ref "IC1") (pin "32") (pinfunction "PD2(INT0)_32") (pintype "bidirectional"))
    )
    (net (code "80") (name "unconnected-(IC1-PD3(INT1)-Pad1)") (class "Default")
      (node (ref "IC1") (pin "1") (pinfunction "PD3(INT1)_1") (pintype "bidirectional"))
    )
    (net (code "81") (name "unconnected-(IC1-PD4(XCK{slash}T0)-Pad2)") (class "Default")
      (node (ref "IC1") (pin "2") (pinfunction "PD4(XCK/T0)_2") (pintype "bidirectional"))
    )
    (net (code "82") (name "unconnected-(IC1-PD5(T1)-Pad9)") (class "Default")
      (node (ref "IC1") (pin "9") (pinfunction "PD5(T1)_9") (pintype "bidirectional"))
    )
    (net (code "83") (name "unconnected-(IC1-PD6(AIN0)-Pad10)") (class "Default")
      (node (ref "IC1") (pin "10") (pinfunction "PD6(AIN0)_10") (pintype "bidirectional"))
    )
    (net (code "84") (name "unconnected-(IC1-PD7(AIN1)-Pad11)") (class "Default")
      (node (ref "IC1") (pin "11") (pinfunction "PD7(AIN1)_11") (pintype "bidirectional"))
    )
    (net (code "85") (name "unconnected-(IC2-(ADC0)PA0-Pad37)") (class "Default")
      (node (ref "IC2") (pin "37") (pinfunction "(ADC0)PA0_37") (pintype "bidirectional"))
    )
    (net (code "86") (name "unconnected-(IC2-(AIN0{slash}INT2)PB2-Pad42)") (class "Default")
      (node (ref "IC2") (pin "42") (pinfunction "(AIN0/INT2)PB2_42") (pintype "bidirectional"))
    )
    (net (code "87") (name "unconnected-(IC2-(ICP)PD6-Pad15)") (class "Default")
      (node (ref "IC2") (pin "15") (pinfunction "(ICP)PD6_15") (pintype "bidirectional"))
    )
    (net (code "88") (name "unconnected-(IC2-(OC1A)PD5-Pad14)") (class "Default")
      (node (ref "IC2") (pin "14") (pinfunction "(OC1A)PD5_14") (pintype "bidirectional"))
    )
    (net (code "89") (name "unconnected-(IC2-(OC2)PD7-Pad16)") (class "Default")
      (node (ref "IC2") (pin "16") (pinfunction "(OC2)PD7_16") (pintype "bidirectional"))
    )
    (net (code "90") (name "unconnected-(IC2-(T0{slash}XCK)PB0-Pad40)") (class "Default")
      (node (ref "IC2") (pin "40") (pinfunction "(T0/XCK)PB0_40") (pintype "bidirectional"))
    )
    (net (code "91") (name "unconnected-(IC2-(T1)PB1-Pad41)") (class "Default")
      (node (ref "IC2") (pin "41") (pinfunction "(T1)PB1_41") (pintype "bidirectional"))
    )
    (net (code "92") (name "unconnected-(IC2-(TCK)PC2-Pad21)") (class "Default")
      (node (ref "IC2") (pin "21") (pinfunction "(TCK)PC2_21") (pintype "bidirectional"))
    )
    (net (code "93") (name "unconnected-(IC2-(TMS)PC3-Pad22)") (class "Default")
      (node (ref "IC2") (pin "22") (pinfunction "(TMS)PC3_22") (pintype "bidirectional"))
    )
    (net (code "94") (name "unconnected-(IC2-AREF-Pad29)") (class "Default")
      (node (ref "IC2") (pin "29") (pinfunction "AREF_29") (pintype "passive"))
    )
    (net (code "95") (name "unconnected-(IC3-ADC6-Pad19)") (class "Default")
      (node (ref "IC3") (pin "19") (pinfunction "ADC6_19") (pintype "bidirectional"))
    )
    (net (code "96") (name "unconnected-(IC3-ADC7-Pad22)") (class "Default")
      (node (ref "IC3") (pin "22") (pinfunction "ADC7_22") (pintype "bidirectional"))
    )
    (net (code "97") (name "unconnected-(IC3-AREF-Pad20)") (class "Default")
      (node (ref "IC3") (pin "20") (pinfunction "AREF_20") (pintype "passive"))
    )
    (net (code "98") (name "unconnected-(IC3-PB0(ICP)-Pad12)") (class "Default")
      (node (ref "IC3") (pin "12") (pinfunction "PB0(ICP)_12") (pintype "bidirectional"))
    )
    (net (code "99") (name "unconnected-(IC3-PB1(OC1A)-Pad13)") (class "Default")
      (node (ref "IC3") (pin "13") (pinfunction "PB1(OC1A)_13") (pintype "bidirectional"))
    )
    (net (code "100") (name "unconnected-(IC3-PB2(SS{slash}OC1B)-Pad14)") (class "Default")
      (node (ref "IC3") (pin "14") (pinfunction "PB2(SS/OC1B)_14") (pintype "bidirectional"))
    )
    (net (code "101") (name "unconnected-(IC3-PB7(XTAL2{slash}TOSC2)-Pad8)") (class "Default")
      (node (ref "IC3") (pin "8") (pinfunction "PB7(XTAL2/TOSC2)_8") (pintype "bidirectional"))
    )
    (net (code "102") (name "unconnected-(IC3-PC1(ADC1)-Pad24)") (class "Default")
      (node (ref "IC3") (pin "24") (pinfunction "PC1(ADC1)_24") (pintype "bidirectional"))
    )
    (net (code "103") (name "unconnected-(IC3-PC2(ADC2)-Pad25)") (class "Default")
      (node (ref "IC3") (pin "25") (pinfunction "PC2(ADC2)_25") (pintype "bidirectional"))
    )
    (net (code "104") (name "unconnected-(IC3-PC3(ADC3)-Pad26)") (class "Default")
      (node (ref "IC3") (pin "26") (pinfunction "PC3(ADC3)_26") (pintype "bidirectional"))
    )
    (net (code "105") (name "unconnected-(IC3-PD2(INT0)-Pad32)") (class "Default")
      (node (ref "IC3") (pin "32") (pinfunction "PD2(INT0)_32") (pintype "bidirectional"))
    )
    (net (code "106") (name "unconnected-(IC3-PD3(INT1)-Pad1)") (class "Default")
      (node (ref "IC3") (pin "1") (pinfunction "PD3(INT1)_1") (pintype "bidirectional"))
    )
    (net (code "107") (name "unconnected-(IC3-PD4(XCK{slash}T0)-Pad2)") (class "Default")
      (node (ref "IC3") (pin "2") (pinfunction "PD4(XCK/T0)_2") (pintype "bidirectional"))
    )
    (net (code "108") (name "unconnected-(IC3-PD5(T1)-Pad9)") (class "Default")
      (node (ref "IC3") (pin "9") (pinfunction "PD5(T1)_9") (pintype "bidirectional"))
    )
    (net (code "109") (name "unconnected-(IC3-PD6(AIN0)-Pad10)") (class "Default")
      (node (ref "IC3") (pin "10") (pinfunction "PD6(AIN0)_10") (pintype "bidirectional"))
    )
    (net (code "110") (name "unconnected-(IC3-PD7(AIN1)-Pad11)") (class "Default")
      (node (ref "IC3") (pin "11") (pinfunction "PD7(AIN1)_11") (pintype "bidirectional"))
    )
    (net (code "111") (name "unconnected-(IC5-CD+-Pad9)") (class "Default")
      (node (ref "IC5") (pin "9") (pinfunction "CD+_9") (pintype "passive"))
    )
    (net (code "112") (name "unconnected-(IC5-O5-Pad12)") (class "Default")
      (node (ref "IC5") (pin "12") (pinfunction "O5_12") (pintype "open_collector"))
    )
    (net (code "113") (name "unconnected-(IC5-O6-Pad11)") (class "Default")
      (node (ref "IC5") (pin "11") (pinfunction "O6_11") (pintype "open_collector"))
    )
    (net (code "114") (name "unconnected-(IC5-O7-Pad10)") (class "Default")
      (node (ref "IC5") (pin "10") (pinfunction "O7_10") (pintype "open_collector"))
    )
    (net (code "115") (name "unconnected-(J1AA-MS-PadC28)") (class "Default")
      (node (ref "J1") (pin "C28") (pinfunction "MS_C28") (pintype "passive"))
    )
    (net (code "116") (name "unconnected-(J1AD-MS-PadC4)") (class "Default")
      (node (ref "J1") (pin "C4") (pinfunction "MS_C4") (pintype "passive"))
    )
    (net (code "117") (name "unconnected-(J1AE-MS-PadC6)") (class "Default")
      (node (ref "J1") (pin "C6") (pinfunction "MS_C6") (pintype "passive"))
    )
    (net (code "118") (name "unconnected-(J1D-MS-PadA16)") (class "Default")
      (node (ref "J1") (pin "A16") (pinfunction "MS_A16") (pintype "passive"))
    )
    (net (code "119") (name "unconnected-(J1I-MS-PadA24)") (class "Default")
      (node (ref "J1") (pin "A24") (pinfunction "MS_A24") (pintype "passive"))
    )
    (net (code "120") (name "unconnected-(J1J-MS-PadA26)") (class "Default")
      (node (ref "J1") (pin "A26") (pinfunction "MS_A26") (pintype "passive"))
    )
    (net (code "121") (name "unconnected-(J1K-MS-PadA28)") (class "Default")
      (node (ref "J1") (pin "A28") (pinfunction "MS_A28") (pintype "passive"))
    )
    (net (code "122") (name "unconnected-(J1N-MS-PadA4)") (class "Default")
      (node (ref "J1") (pin "A4") (pinfunction "MS_A4") (pintype "passive"))
    )
    (net (code "123") (name "unconnected-(J1Y-MS-PadC24)") (class "Default")
      (node (ref "J1") (pin "C24") (pinfunction "MS_C24") (pintype "passive"))
    )
    (net (code "124") (name "unconnected-(J1Z-MS-PadC26)") (class "Default")
      (node (ref "J1") (pin "C26") (pinfunction "MS_C26") (pintype "passive"))
    )
  )
)
